# PCB1.net
KiCad netlist of a schematic drawn in EAGLE
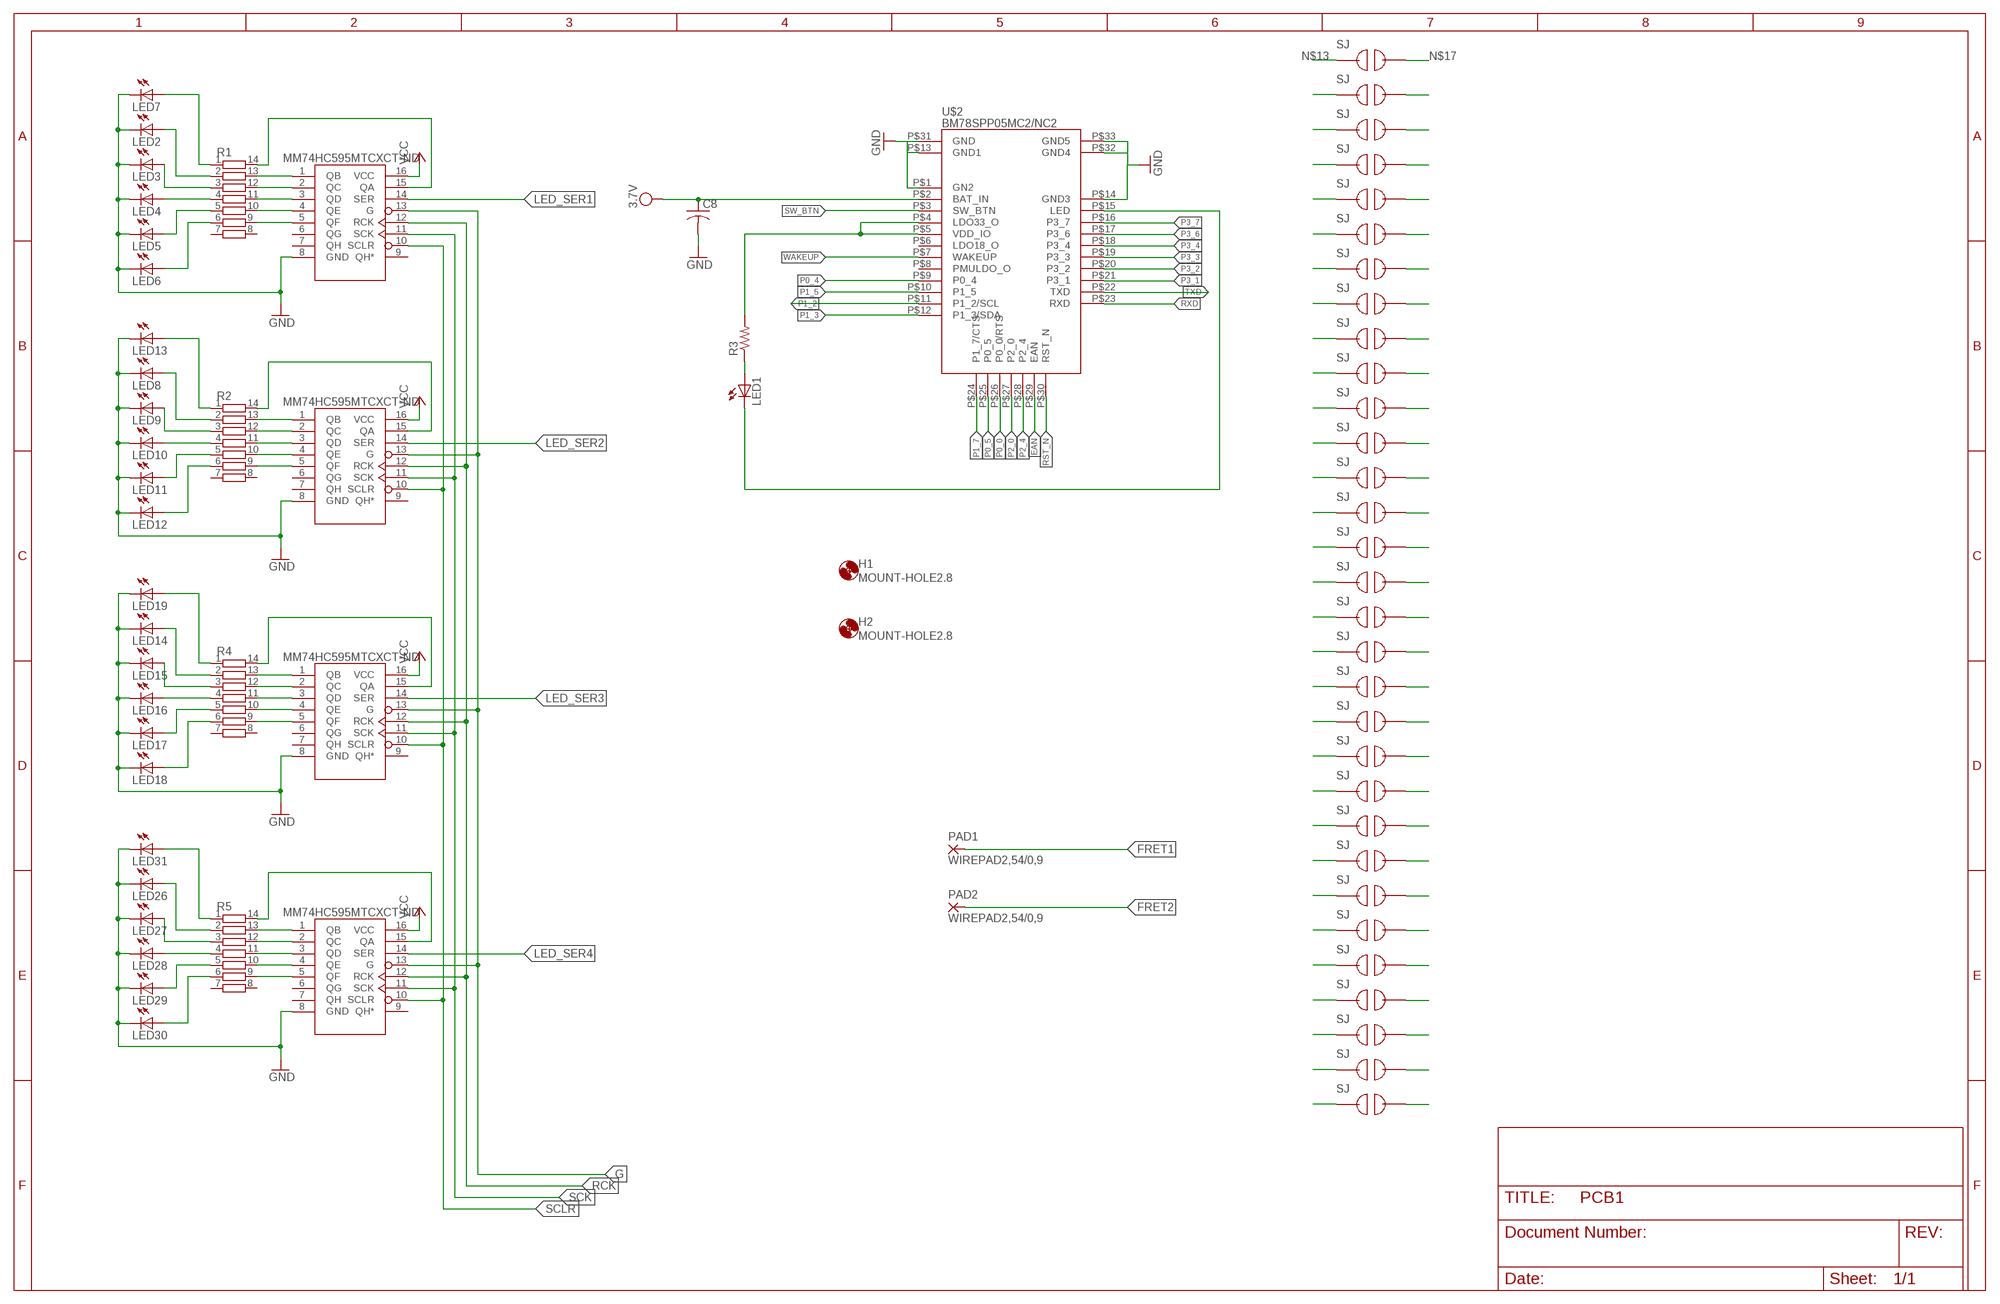
[diagram p0: schematic, sheet 1]

(export (version "E")
  (design (tool "Eeschema 10.0.6"))
  (components
    (comp (ref "C8")
      (value "C-USC0805")
      (footprint "eagle-import:C0805")
      (libsource (lib "eagle-import") (part "C-USC0805"))
    )
    (comp (ref "H1")
      (value "MOUNT-HOLE2.8")
      (footprint "eagle-import:2,8")
      (libsource (lib "eagle-import") (part "MOUNT-HOLE2.8"))
    )
    (comp (ref "H2")
      (value "MOUNT-HOLE2.8")
      (footprint "eagle-import:2,8")
      (libsource (lib "eagle-import") (part "MOUNT-HOLE2.8"))
    )
    (comp (ref "LED1")
      (value "LEDSMT1206")
      (footprint "eagle-import:1206")
      (libsource (lib "eagle-import") (part "LEDSMT1206"))
    )
    (comp (ref "LED2")
      (value "LEDSMT1206")
      (footprint "eagle-import:1206")
      (libsource (lib "eagle-import") (part "LEDSMT1206"))
    )
    (comp (ref "LED3")
      (value "LEDSMT1206")
      (footprint "eagle-import:1206")
      (libsource (lib "eagle-import") (part "LEDSMT1206"))
    )
    (comp (ref "LED4")
      (value "LEDSMT1206")
      (footprint "eagle-import:1206")
      (libsource (lib "eagle-import") (part "LEDSMT1206"))
    )
    (comp (ref "LED5")
      (value "LEDSMT1206")
      (footprint "eagle-import:1206")
      (libsource (lib "eagle-import") (part "LEDSMT1206"))
    )
    (comp (ref "LED6")
      (value "LEDSMT1206")
      (footprint "eagle-import:1206")
      (libsource (lib "eagle-import") (part "LEDSMT1206"))
    )
    (comp (ref "LED7")
      (value "LEDSMT1206")
      (footprint "eagle-import:1206")
      (libsource (lib "eagle-import") (part "LEDSMT1206"))
    )
    (comp (ref "LED8")
      (value "LEDSMT1206")
      (footprint "eagle-import:1206")
      (libsource (lib "eagle-import") (part "LEDSMT1206"))
    )
    (comp (ref "LED9")
      (value "LEDSMT1206")
      (footprint "eagle-import:1206")
      (libsource (lib "eagle-import") (part "LEDSMT1206"))
    )
    (comp (ref "LED10")
      (value "LEDSMT1206")
      (footprint "eagle-import:1206")
      (libsource (lib "eagle-import") (part "LEDSMT1206"))
    )
    (comp (ref "LED11")
      (value "LEDSMT1206")
      (footprint "eagle-import:1206")
      (libsource (lib "eagle-import") (part "LEDSMT1206"))
    )
    (comp (ref "LED12")
      (value "LEDSMT1206")
      (footprint "eagle-import:1206")
      (libsource (lib "eagle-import") (part "LEDSMT1206"))
    )
    (comp (ref "LED13")
      (value "LEDSMT1206")
      (footprint "eagle-import:1206")
      (libsource (lib "eagle-import") (part "LEDSMT1206"))
    )
    (comp (ref "LED14")
      (value "LEDSMT1206")
      (footprint "eagle-import:1206")
      (libsource (lib "eagle-import") (part "LEDSMT1206"))
    )
    (comp (ref "LED15")
      (value "LEDSMT1206")
      (footprint "eagle-import:1206")
      (libsource (lib "eagle-import") (part "LEDSMT1206"))
    )
    (comp (ref "LED16")
      (value "LEDSMT1206")
      (footprint "eagle-import:1206")
      (libsource (lib "eagle-import") (part "LEDSMT1206"))
    )
    (comp (ref "LED17")
      (value "LEDSMT1206")
      (footprint "eagle-import:1206")
      (libsource (lib "eagle-import") (part "LEDSMT1206"))
    )
    (comp (ref "LED18")
      (value "LEDSMT1206")
      (footprint "eagle-import:1206")
      (libsource (lib "eagle-import") (part "LEDSMT1206"))
    )
    (comp (ref "LED19")
      (value "LEDSMT1206")
      (footprint "eagle-import:1206")
      (libsource (lib "eagle-import") (part "LEDSMT1206"))
    )
    (comp (ref "LED26")
      (value "LEDSMT1206")
      (footprint "eagle-import:1206")
      (libsource (lib "eagle-import") (part "LEDSMT1206"))
    )
    (comp (ref "LED27")
      (value "LEDSMT1206")
      (footprint "eagle-import:1206")
      (libsource (lib "eagle-import") (part "LEDSMT1206"))
    )
    (comp (ref "LED28")
      (value "LEDSMT1206")
      (footprint "eagle-import:1206")
      (libsource (lib "eagle-import") (part "LEDSMT1206"))
    )
    (comp (ref "LED29")
      (value "LEDSMT1206")
      (footprint "eagle-import:1206")
      (libsource (lib "eagle-import") (part "LEDSMT1206"))
    )
    (comp (ref "LED30")
      (value "LEDSMT1206")
      (footprint "eagle-import:1206")
      (libsource (lib "eagle-import") (part "LEDSMT1206"))
    )
    (comp (ref "LED31")
      (value "LEDSMT1206")
      (footprint "eagle-import:1206")
      (libsource (lib "eagle-import") (part "LEDSMT1206"))
    )
    (comp (ref "PAD1")
      (value "WIREPAD2,54/0,9")
      (footprint "eagle-import:2,54_0,9")
      (libsource (lib "eagle-import") (part "WIREPAD2,54/0,9"))
    )
    (comp (ref "PAD2")
      (value "WIREPAD2,54/0,9")
      (footprint "eagle-import:2,54_0,9")
      (libsource (lib "eagle-import") (part "WIREPAD2,54/0,9"))
    )
    (comp (ref "R1")
      (value "4814P-T01")
      (footprint "eagle-import:4814P")
      (fields (field (name "MF") "BOURNS, INC.") (field (name "MPN") "4814P-T01-104LF"))
      (libsource (lib "eagle-import") (part "4814P-T01"))
    )
    (comp (ref "R2")
      (value "4814P-T01")
      (footprint "eagle-import:4814P")
      (fields (field (name "MF") "BOURNS, INC.") (field (name "MPN") "4814P-T01-104LF"))
      (libsource (lib "eagle-import") (part "4814P-T01"))
    )
    (comp (ref "R3")
      (value "R-US_M0805")
      (footprint "eagle-import:M0805")
      (libsource (lib "eagle-import") (part "R-US_M0805"))
    )
    (comp (ref "R4")
      (value "4814P-T01")
      (footprint "eagle-import:4814P")
      (fields (field (name "MF") "BOURNS, INC.") (field (name "MPN") "4814P-T01-104LF"))
      (libsource (lib "eagle-import") (part "4814P-T01"))
    )
    (comp (ref "R5")
      (value "4814P-T01")
      (footprint "eagle-import:4814P")
      (fields (field (name "MF") "BOURNS, INC.") (field (name "MPN") "4814P-T01-104LF"))
      (libsource (lib "eagle-import") (part "4814P-T01"))
    )
    (comp (ref "U$1")
      (value "MM74HC595TSSOP-LD16")
      (footprint "eagle-import:MM74HC595MTCXCT-ND")
      (libsource (lib "eagle-import") (part "MM74HC595TSSOP-LD16"))
    )
    (comp (ref "U$2")
      (value "BM78SPP05MC2/NC2")
      (footprint "eagle-import:BM78SPP05MC2_NC2")
      (libsource (lib "eagle-import") (part "BM78SPP05MC2/NC2"))
    )
    (comp (ref "U$3")
      (value "MM74HC595TSSOP-LD16")
      (footprint "eagle-import:MM74HC595MTCXCT-ND")
      (libsource (lib "eagle-import") (part "MM74HC595TSSOP-LD16"))
    )
    (comp (ref "U$4")
      (value "MM74HC595TSSOP-LD16")
      (footprint "eagle-import:MM74HC595MTCXCT-ND")
      (libsource (lib "eagle-import") (part "MM74HC595TSSOP-LD16"))
    )
    (comp (ref "U$5")
      (value "MM74HC595TSSOP-LD16")
      (footprint "eagle-import:MM74HC595MTCXCT-ND")
      (libsource (lib "eagle-import") (part "MM74HC595TSSOP-LD16"))
    )
    (comp (ref "U$6")
      (value "JUMPER")
      (footprint "eagle-import:JUMPER")
      (libsource (lib "eagle-import") (part "JUMPER"))
    )
    (comp (ref "U$7")
      (value "JUMPER")
      (footprint "eagle-import:JUMPER")
      (libsource (lib "eagle-import") (part "JUMPER"))
    )
    (comp (ref "U$8")
      (value "JUMPER")
      (footprint "eagle-import:JUMPER")
      (libsource (lib "eagle-import") (part "JUMPER"))
    )
    (comp (ref "U$9")
      (value "JUMPER")
      (footprint "eagle-import:JUMPER")
      (libsource (lib "eagle-import") (part "JUMPER"))
    )
    (comp (ref "U$10")
      (value "JUMPER")
      (footprint "eagle-import:JUMPER")
      (libsource (lib "eagle-import") (part "JUMPER"))
    )
    (comp (ref "U$11")
      (value "JUMPER")
      (footprint "eagle-import:JUMPER")
      (libsource (lib "eagle-import") (part "JUMPER"))
    )
    (comp (ref "U$12")
      (value "JUMPER")
      (footprint "eagle-import:JUMPER")
      (libsource (lib "eagle-import") (part "JUMPER"))
    )
    (comp (ref "U$13")
      (value "JUMPER")
      (footprint "eagle-import:JUMPER")
      (libsource (lib "eagle-import") (part "JUMPER"))
    )
    (comp (ref "U$14")
      (value "JUMPER")
      (footprint "eagle-import:JUMPER")
      (libsource (lib "eagle-import") (part "JUMPER"))
    )
    (comp (ref "U$15")
      (value "JUMPER")
      (footprint "eagle-import:JUMPER")
      (libsource (lib "eagle-import") (part "JUMPER"))
    )
    (comp (ref "U$16")
      (value "JUMPER")
      (footprint "eagle-import:JUMPER")
      (libsource (lib "eagle-import") (part "JUMPER"))
    )
    (comp (ref "U$17")
      (value "JUMPER")
      (footprint "eagle-import:JUMPER")
      (libsource (lib "eagle-import") (part "JUMPER"))
    )
    (comp (ref "U$18")
      (value "JUMPER")
      (footprint "eagle-import:JUMPER")
      (libsource (lib "eagle-import") (part "JUMPER"))
    )
    (comp (ref "U$19")
      (value "JUMPER")
      (footprint "eagle-import:JUMPER")
      (libsource (lib "eagle-import") (part "JUMPER"))
    )
    (comp (ref "U$20")
      (value "JUMPER")
      (footprint "eagle-import:JUMPER")
      (libsource (lib "eagle-import") (part "JUMPER"))
    )
    (comp (ref "U$21")
      (value "JUMPER")
      (footprint "eagle-import:JUMPER")
      (libsource (lib "eagle-import") (part "JUMPER"))
    )
    (comp (ref "U$22")
      (value "JUMPER")
      (footprint "eagle-import:JUMPER")
      (libsource (lib "eagle-import") (part "JUMPER"))
    )
    (comp (ref "U$23")
      (value "JUMPER")
      (footprint "eagle-import:JUMPER")
      (libsource (lib "eagle-import") (part "JUMPER"))
    )
    (comp (ref "U$24")
      (value "JUMPER")
      (footprint "eagle-import:JUMPER")
      (libsource (lib "eagle-import") (part "JUMPER"))
    )
    (comp (ref "U$25")
      (value "JUMPER")
      (footprint "eagle-import:JUMPER")
      (libsource (lib "eagle-import") (part "JUMPER"))
    )
    (comp (ref "U$26")
      (value "JUMPER")
      (footprint "eagle-import:JUMPER")
      (libsource (lib "eagle-import") (part "JUMPER"))
    )
    (comp (ref "U$27")
      (value "JUMPER")
      (footprint "eagle-import:JUMPER")
      (libsource (lib "eagle-import") (part "JUMPER"))
    )
    (comp (ref "U$28")
      (value "JUMPER")
      (footprint "eagle-import:JUMPER")
      (libsource (lib "eagle-import") (part "JUMPER"))
    )
    (comp (ref "U$29")
      (value "JUMPER")
      (footprint "eagle-import:JUMPER")
      (libsource (lib "eagle-import") (part "JUMPER"))
    )
    (comp (ref "U$30")
      (value "JUMPER")
      (footprint "eagle-import:JUMPER")
      (libsource (lib "eagle-import") (part "JUMPER"))
    )
    (comp (ref "U$31")
      (value "JUMPER")
      (footprint "eagle-import:JUMPER")
      (libsource (lib "eagle-import") (part "JUMPER"))
    )
    (comp (ref "U$32")
      (value "JUMPER")
      (footprint "eagle-import:JUMPER")
      (libsource (lib "eagle-import") (part "JUMPER"))
    )
    (comp (ref "U$33")
      (value "JUMPER")
      (footprint "eagle-import:JUMPER")
      (libsource (lib "eagle-import") (part "JUMPER"))
    )
    (comp (ref "U$34")
      (value "JUMPER")
      (footprint "eagle-import:JUMPER")
      (libsource (lib "eagle-import") (part "JUMPER"))
    )
    (comp (ref "U$35")
      (value "JUMPER")
      (footprint "eagle-import:JUMPER")
      (libsource (lib "eagle-import") (part "JUMPER"))
    )
    (comp (ref "U$36")
      (value "JUMPER")
      (footprint "eagle-import:JUMPER")
      (libsource (lib "eagle-import") (part "JUMPER"))
    )
  )
  (nets
    (net (code "1") (name "/N$13") (class "Default")
      (node (ref "U$35") (pin "P$1") (pinfunction "P$1_P$1") (pintype "bidirectional"))
    )
    (net (code "2") (name "/N$17") (class "Default")
      (node (ref "U$35") (pin "P$2") (pinfunction "P$2_P$2") (pintype "bidirectional"))
    )
    (net (code "3") (name "3.7V") (class "Default")
      (node (ref "C8") (pin "1") (pinfunction "1_1") (pintype "passive"))
      (node (ref "U$2") (pin "P$2") (pinfunction "BAT_IN_P$2") (pintype "bidirectional"))
    )
    (net (code "4") (name "EAN") (class "Default")
      (node (ref "U$2") (pin "P$29") (pinfunction "EAN_P$29") (pintype "bidirectional"))
    )
    (net (code "5") (name "FRET1") (class "Default")
      (node (ref "PAD1") (pin "1") (pinfunction "P_1") (pintype "passive"))
    )
    (net (code "6") (name "FRET2") (class "Default")
      (node (ref "PAD2") (pin "1") (pinfunction "P_1") (pintype "passive"))
    )
    (net (code "7") (name "G") (class "Default")
      (node (ref "U$1") (pin "13") (pinfunction "G_13") (pintype "bidirectional"))
      (node (ref "U$3") (pin "13") (pinfunction "G_13") (pintype "bidirectional"))
      (node (ref "U$4") (pin "13") (pinfunction "G_13") (pintype "bidirectional"))
      (node (ref "U$5") (pin "13") (pinfunction "G_13") (pintype "bidirectional"))
    )
    (net (code "8") (name "GND") (class "Default")
      (node (ref "C8") (pin "2") (pinfunction "2_2") (pintype "passive"))
      (node (ref "LED10") (pin "C") (pinfunction "C_C") (pintype "passive"))
      (node (ref "LED11") (pin "C") (pinfunction "C_C") (pintype "passive"))
      (node (ref "LED12") (pin "C") (pinfunction "C_C") (pintype "passive"))
      (node (ref "LED13") (pin "C") (pinfunction "C_C") (pintype "passive"))
      (node (ref "LED14") (pin "C") (pinfunction "C_C") (pintype "passive"))
      (node (ref "LED15") (pin "C") (pinfunction "C_C") (pintype "passive"))
      (node (ref "LED16") (pin "C") (pinfunction "C_C") (pintype "passive"))
      (node (ref "LED17") (pin "C") (pinfunction "C_C") (pintype "passive"))
      (node (ref "LED18") (pin "C") (pinfunction "C_C") (pintype "passive"))
      (node (ref "LED19") (pin "C") (pinfunction "C_C") (pintype "passive"))
      (node (ref "LED2") (pin "C") (pinfunction "C_C") (pintype "passive"))
      (node (ref "LED26") (pin "C") (pinfunction "C_C") (pintype "passive"))
      (node (ref "LED27") (pin "C") (pinfunction "C_C") (pintype "passive"))
      (node (ref "LED28") (pin "C") (pinfunction "C_C") (pintype "passive"))
      (node (ref "LED29") (pin "C") (pinfunction "C_C") (pintype "passive"))
      (node (ref "LED3") (pin "C") (pinfunction "C_C") (pintype "passive"))
      (node (ref "LED30") (pin "C") (pinfunction "C_C") (pintype "passive"))
      (node (ref "LED31") (pin "C") (pinfunction "C_C") (pintype "passive"))
      (node (ref "LED4") (pin "C") (pinfunction "C_C") (pintype "passive"))
      (node (ref "LED5") (pin "C") (pinfunction "C_C") (pintype "passive"))
      (node (ref "LED6") (pin "C") (pinfunction "C_C") (pintype "passive"))
      (node (ref "LED7") (pin "C") (pinfunction "C_C") (pintype "passive"))
      (node (ref "LED8") (pin "C") (pinfunction "C_C") (pintype "passive"))
      (node (ref "LED9") (pin "C") (pinfunction "C_C") (pintype "passive"))
      (node (ref "U$1") (pin "8") (pinfunction "GND_8") (pintype "bidirectional"))
      (node (ref "U$2") (pin "P$1") (pinfunction "GN2_P$1") (pintype "bidirectional"))
      (node (ref "U$2") (pin "P$13") (pinfunction "GND1_P$13") (pintype "bidirectional"))
      (node (ref "U$2") (pin "P$14") (pinfunction "GND3_P$14") (pintype "bidirectional"))
      (node (ref "U$2") (pin "P$31") (pinfunction "GND_P$31") (pintype "bidirectional"))
      (node (ref "U$2") (pin "P$32") (pinfunction "GND4_P$32") (pintype "bidirectional"))
      (node (ref "U$2") (pin "P$33") (pinfunction "GND5_P$33") (pintype "bidirectional"))
      (node (ref "U$3") (pin "8") (pinfunction "GND_8") (pintype "bidirectional"))
      (node (ref "U$4") (pin "8") (pinfunction "GND_8") (pintype "bidirectional"))
      (node (ref "U$5") (pin "8") (pinfunction "GND_8") (pintype "bidirectional"))
    )
    (net (code "9") (name "LED_SER1") (class "Default")
      (node (ref "U$4") (pin "14") (pinfunction "SER_14") (pintype "bidirectional"))
    )
    (net (code "10") (name "LED_SER2") (class "Default")
      (node (ref "U$1") (pin "14") (pinfunction "SER_14") (pintype "bidirectional"))
    )
    (net (code "11") (name "LED_SER3") (class "Default")
      (node (ref "U$3") (pin "14") (pinfunction "SER_14") (pintype "bidirectional"))
    )
    (net (code "12") (name "LED_SER4") (class "Default")
      (node (ref "U$5") (pin "14") (pinfunction "SER_14") (pintype "bidirectional"))
    )
    (net (code "13") (name "Net-(LED1-PadA)") (class "Default")
      (node (ref "LED1") (pin "A") (pinfunction "A_A") (pintype "passive"))
      (node (ref "R3") (pin "1") (pinfunction "1_1") (pintype "passive"))
    )
    (net (code "14") (name "Net-(LED2-PadA)") (class "Default")
      (node (ref "LED2") (pin "A") (pinfunction "A_A") (pintype "passive"))
      (node (ref "R1") (pin "2") (pinfunction "2_2") (pintype "passive"))
    )
    (net (code "15") (name "Net-(LED3-PadA)") (class "Default")
      (node (ref "LED3") (pin "A") (pinfunction "A_A") (pintype "passive"))
      (node (ref "R1") (pin "3") (pinfunction "3_3") (pintype "passive"))
    )
    (net (code "16") (name "Net-(LED4-PadA)") (class "Default")
      (node (ref "LED4") (pin "A") (pinfunction "A_A") (pintype "passive"))
      (node (ref "R1") (pin "4") (pinfunction "4_4") (pintype "passive"))
    )
    (net (code "17") (name "Net-(LED5-PadA)") (class "Default")
      (node (ref "LED5") (pin "A") (pinfunction "A_A") (pintype "passive"))
      (node (ref "R1") (pin "5") (pinfunction "5_5") (pintype "passive"))
    )
    (net (code "18") (name "Net-(LED6-PadA)") (class "Default")
      (node (ref "LED6") (pin "A") (pinfunction "A_A") (pintype "passive"))
      (node (ref "R1") (pin "6") (pinfunction "6_6") (pintype "passive"))
    )
    (net (code "19") (name "Net-(LED7-PadA)") (class "Default")
      (node (ref "LED7") (pin "A") (pinfunction "A_A") (pintype "passive"))
      (node (ref "R1") (pin "1") (pinfunction "1_1") (pintype "passive"))
    )
    (net (code "20") (name "Net-(LED8-PadA)") (class "Default")
      (node (ref "LED8") (pin "A") (pinfunction "A_A") (pintype "passive"))
      (node (ref "R2") (pin "2") (pinfunction "2_2") (pintype "passive"))
    )
    (net (code "21") (name "Net-(LED9-PadA)") (class "Default")
      (node (ref "LED9") (pin "A") (pinfunction "A_A") (pintype "passive"))
      (node (ref "R2") (pin "3") (pinfunction "3_3") (pintype "passive"))
    )
    (net (code "22") (name "Net-(LED10-PadA)") (class "Default")
      (node (ref "LED10") (pin "A") (pinfunction "A_A") (pintype "passive"))
      (node (ref "R2") (pin "4") (pinfunction "4_4") (pintype "passive"))
    )
    (net (code "23") (name "Net-(LED11-PadA)") (class "Default")
      (node (ref "LED11") (pin "A") (pinfunction "A_A") (pintype "passive"))
      (node (ref "R2") (pin "5") (pinfunction "5_5") (pintype "passive"))
    )
    (net (code "24") (name "Net-(LED12-PadA)") (class "Default")
      (node (ref "LED12") (pin "A") (pinfunction "A_A") (pintype "passive"))
      (node (ref "R2") (pin "6") (pinfunction "6_6") (pintype "passive"))
    )
    (net (code "25") (name "Net-(LED13-PadA)") (class "Default")
      (node (ref "LED13") (pin "A") (pinfunction "A_A") (pintype "passive"))
      (node (ref "R2") (pin "1") (pinfunction "1_1") (pintype "passive"))
    )
    (net (code "26") (name "Net-(LED14-PadA)") (class "Default")
      (node (ref "LED14") (pin "A") (pinfunction "A_A") (pintype "passive"))
      (node (ref "R4") (pin "2") (pinfunction "2_2") (pintype "passive"))
    )
    (net (code "27") (name "Net-(LED15-PadA)") (class "Default")
      (node (ref "LED15") (pin "A") (pinfunction "A_A") (pintype "passive"))
      (node (ref "R4") (pin "3") (pinfunction "3_3") (pintype "passive"))
    )
    (net (code "28") (name "Net-(LED16-PadA)") (class "Default")
      (node (ref "LED16") (pin "A") (pinfunction "A_A") (pintype "passive"))
      (node (ref "R4") (pin "4") (pinfunction "4_4") (pintype "passive"))
    )
    (net (code "29") (name "Net-(LED17-PadA)") (class "Default")
      (node (ref "LED17") (pin "A") (pinfunction "A_A") (pintype "passive"))
      (node (ref "R4") (pin "5") (pinfunction "5_5") (pintype "passive"))
    )
    (net (code "30") (name "Net-(LED18-PadA)") (class "Default")
      (node (ref "LED18") (pin "A") (pinfunction "A_A") (pintype "passive"))
      (node (ref "R4") (pin "6") (pinfunction "6_6") (pintype "passive"))
    )
    (net (code "31") (name "Net-(LED19-PadA)") (class "Default")
      (node (ref "LED19") (pin "A") (pinfunction "A_A") (pintype "passive"))
      (node (ref "R4") (pin "1") (pinfunction "1_1") (pintype "passive"))
    )
    (net (code "32") (name "Net-(LED26-PadA)") (class "Default")
      (node (ref "LED26") (pin "A") (pinfunction "A_A") (pintype "passive"))
      (node (ref "R5") (pin "2") (pinfunction "2_2") (pintype "passive"))
    )
    (net (code "33") (name "Net-(LED27-PadA)") (class "Default")
      (node (ref "LED27") (pin "A") (pinfunction "A_A") (pintype "passive"))
      (node (ref "R5") (pin "3") (pinfunction "3_3") (pintype "passive"))
    )
    (net (code "34") (name "Net-(LED28-PadA)") (class "Default")
      (node (ref "LED28") (pin "A") (pinfunction "A_A") (pintype "passive"))
      (node (ref "R5") (pin "4") (pinfunction "4_4") (pintype "passive"))
    )
    (net (code "35") (name "Net-(LED29-PadA)") (class "Default")
      (node (ref "LED29") (pin "A") (pinfunction "A_A") (pintype "passive"))
      (node (ref "R5") (pin "5") (pinfunction "5_5") (pintype "passive"))
    )
    (net (code "36") (name "Net-(LED30-PadA)") (class "Default")
      (node (ref "LED30") (pin "A") (pinfunction "A_A") (pintype "passive"))
      (node (ref "R5") (pin "6") (pinfunction "6_6") (pintype "passive"))
    )
    (net (code "37") (name "Net-(LED31-PadA)") (class "Default")
      (node (ref "LED31") (pin "A") (pinfunction "A_A") (pintype "passive"))
      (node (ref "R5") (pin "1") (pinfunction "1_1") (pintype "passive"))
    )
    (net (code "38") (name "Net-(U$1-QA)") (class "Default")
      (node (ref "R2") (pin "14") (pinfunction "14_14") (pintype "passive"))
      (node (ref "U$1") (pin "15") (pinfunction "QA_15") (pintype "bidirectional"))
    )
    (net (code "39") (name "Net-(U$1-QB)") (class "Default")
      (node (ref "R2") (pin "13") (pinfunction "13_13") (pintype "passive"))
      (node (ref "U$1") (pin "1") (pinfunction "QB_1") (pintype "bidirectional"))
    )
    (net (code "40") (name "Net-(U$1-QC)") (class "Default")
      (node (ref "R2") (pin "12") (pinfunction "12_12") (pintype "passive"))
      (node (ref "U$1") (pin "2") (pinfunction "QC_2") (pintype "bidirectional"))
    )
    (net (code "41") (name "Net-(U$1-QD)") (class "Default")
      (node (ref "R2") (pin "11") (pinfunction "11_11") (pintype "passive"))
      (node (ref "U$1") (pin "3") (pinfunction "QD_3") (pintype "bidirectional"))
    )
    (net (code "42") (name "Net-(U$1-QE)") (class "Default")
      (node (ref "R2") (pin "10") (pinfunction "10_10") (pintype "passive"))
      (node (ref "U$1") (pin "4") (pinfunction "QE_4") (pintype "bidirectional"))
    )
    (net (code "43") (name "Net-(U$1-QF)") (class "Default")
      (node (ref "R2") (pin "9") (pinfunction "9_9") (pintype "passive"))
      (node (ref "U$1") (pin "5") (pinfunction "QF_5") (pintype "bidirectional"))
    )
    (net (code "44") (name "Net-(U$2-LDO33_O)") (class "Default")
      (node (ref "R3") (pin "2") (pinfunction "2_2") (pintype "passive"))
      (node (ref "U$2") (pin "P$4") (pinfunction "LDO33_O_P$4") (pintype "bidirectional"))
      (node (ref "U$2") (pin "P$5") (pinfunction "VDD_IO_P$5") (pintype "bidirectional"))
    )
    (net (code "45") (name "Net-(U$2-LED)") (class "Default")
      (node (ref "LED1") (pin "C") (pinfunction "C_C") (pintype "passive"))
      (node (ref "U$2") (pin "P$15") (pinfunction "LED_P$15") (pintype "bidirectional"))
    )
    (net (code "46") (name "Net-(U$3-QA)") (class "Default")
      (node (ref "R4") (pin "14") (pinfunction "14_14") (pintype "passive"))
      (node (ref "U$3") (pin "15") (pinfunction "QA_15") (pintype "bidirectional"))
    )
    (net (code "47") (name "Net-(U$3-QB)") (class "Default")
      (node (ref "R4") (pin "13") (pinfunction "13_13") (pintype "passive"))
      (node (ref "U$3") (pin "1") (pinfunction "QB_1") (pintype "bidirectional"))
    )
    (net (code "48") (name "Net-(U$3-QC)") (class "Default")
      (node (ref "R4") (pin "12") (pinfunction "12_12") (pintype "passive"))
      (node (ref "U$3") (pin "2") (pinfunction "QC_2") (pintype "bidirectional"))
    )
    (net (code "49") (name "Net-(U$3-QD)") (class "Default")
      (node (ref "R4") (pin "11") (pinfunction "11_11") (pintype "passive"))
      (node (ref "U$3") (pin "3") (pinfunction "QD_3") (pintype "bidirectional"))
    )
    (net (code "50") (name "Net-(U$3-QE)") (class "Default")
      (node (ref "R4") (pin "10") (pinfunction "10_10") (pintype "passive"))
      (node (ref "U$3") (pin "4") (pinfunction "QE_4") (pintype "bidirectional"))
    )
    (net (code "51") (name "Net-(U$3-QF)") (class "Default")
      (node (ref "R4") (pin "9") (pinfunction "9_9") (pintype "passive"))
      (node (ref "U$3") (pin "5") (pinfunction "QF_5") (pintype "bidirectional"))
    )
    (net (code "52") (name "Net-(U$4-QA)") (class "Default")
      (node (ref "R1") (pin "14") (pinfunction "14_14") (pintype "passive"))
      (node (ref "U$4") (pin "15") (pinfunction "QA_15") (pintype "bidirectional"))
    )
    (net (code "53") (name "Net-(U$4-QB)") (class "Default")
      (node (ref "R1") (pin "13") (pinfunction "13_13") (pintype "passive"))
      (node (ref "U$4") (pin "1") (pinfunction "QB_1") (pintype "bidirectional"))
    )
    (net (code "54") (name "Net-(U$4-QC)") (class "Default")
      (node (ref "R1") (pin "12") (pinfunction "12_12") (pintype "passive"))
      (node (ref "U$4") (pin "2") (pinfunction "QC_2") (pintype "bidirectional"))
    )
    (net (code "55") (name "Net-(U$4-QD)") (class "Default")
      (node (ref "R1") (pin "11") (pinfunction "11_11") (pintype "passive"))
      (node (ref "U$4") (pin "3") (pinfunction "QD_3") (pintype "bidirectional"))
    )
    (net (code "56") (name "Net-(U$4-QE)") (class "Default")
      (node (ref "R1") (pin "10") (pinfunction "10_10") (pintype "passive"))
      (node (ref "U$4") (pin "4") (pinfunction "QE_4") (pintype "bidirectional"))
    )
    (net (code "57") (name "Net-(U$4-QF)") (class "Default")
      (node (ref "R1") (pin "9") (pinfunction "9_9") (pintype "passive"))
      (node (ref "U$4") (pin "5") (pinfunction "QF_5") (pintype "bidirectional"))
    )
    (net (code "58") (name "Net-(U$5-QA)") (class "Default")
      (node (ref "R5") (pin "14") (pinfunction "14_14") (pintype "passive"))
      (node (ref "U$5") (pin "15") (pinfunction "QA_15") (pintype "bidirectional"))
    )
    (net (code "59") (name "Net-(U$5-QB)") (class "Default")
      (node (ref "R5") (pin "13") (pinfunction "13_13") (pintype "passive"))
      (node (ref "U$5") (pin "1") (pinfunction "QB_1") (pintype "bidirectional"))
    )
    (net (code "60") (name "Net-(U$5-QC)") (class "Default")
      (node (ref "R5") (pin "12") (pinfunction "12_12") (pintype "passive"))
      (node (ref "U$5") (pin "2") (pinfunction "QC_2") (pintype "bidirectional"))
    )
    (net (code "61") (name "Net-(U$5-QD)") (class "Default")
      (node (ref "R5") (pin "11") (pinfunction "11_11") (pintype "passive"))
      (node (ref "U$5") (pin "3") (pinfunction "QD_3") (pintype "bidirectional"))
    )
    (net (code "62") (name "Net-(U$5-QE)") (class "Default")
      (node (ref "R5") (pin "10") (pinfunction "10_10") (pintype "passive"))
      (node (ref "U$5") (pin "4") (pinfunction "QE_4") (pintype "bidirectional"))
    )
    (net (code "63") (name "Net-(U$5-QF)") (class "Default")
      (node (ref "R5") (pin "9") (pinfunction "9_9") (pintype "passive"))
      (node (ref "U$5") (pin "5") (pinfunction "QF_5") (pintype "bidirectional"))
    )
    (net (code "64") (name "P0_0") (class "Default")
      (node (ref "U$2") (pin "P$26") (pinfunction "P0_0/RTS_P$26") (pintype "bidirectional"))
    )
    (net (code "65") (name "P0_4") (class "Default")
      (node (ref "U$2") (pin "P$9") (pinfunction "P0_4_P$9") (pintype "bidirectional"))
    )
    (net (code "66") (name "P0_5") (class "Default")
      (node (ref "U$2") (pin "P$25") (pinfunction "P0_5_P$25") (pintype "bidirectional"))
    )
    (net (code "67") (name "P1_2") (class "Default")
      (node (ref "U$2") (pin "P$11") (pinfunction "P1_2/SCL_P$11") (pintype "bidirectional"))
    )
    (net (code "68") (name "P1_3") (class "Default")
      (node (ref "U$2") (pin "P$12") (pinfunction "P1_3/SDA_P$12") (pintype "bidirectional"))
    )
    (net (code "69") (name "P1_5") (class "Default")
      (node (ref "U$2") (pin "P$10") (pinfunction "P1_5_P$10") (pintype "bidirectional"))
    )
    (net (code "70") (name "P1_7") (class "Default")
      (node (ref "U$2") (pin "P$24") (pinfunction "P1_7/CTS_P$24") (pintype "bidirectional"))
    )
    (net (code "71") (name "P2_0") (class "Default")
      (node (ref "U$2") (pin "P$27") (pinfunction "P2_0_P$27") (pintype "bidirectional"))
    )
    (net (code "72") (name "P2_4") (class "Default")
      (node (ref "U$2") (pin "P$28") (pinfunction "P2_4_P$28") (pintype "bidirectional"))
    )
    (net (code "73") (name "P3_1") (class "Default")
      (node (ref "U$2") (pin "P$21") (pinfunction "P3_1_P$21") (pintype "bidirectional"))
    )
    (net (code "74") (name "P3_2") (class "Default")
      (node (ref "U$2") (pin "P$20") (pinfunction "P3_2_P$20") (pintype "bidirectional"))
    )
    (net (code "75") (name "P3_3") (class "Default")
      (node (ref "U$2") (pin "P$19") (pinfunction "P3_3_P$19") (pintype "bidirectional"))
    )
    (net (code "76") (name "P3_4") (class "Default")
      (node (ref "U$2") (pin "P$18") (pinfunction "P3_4_P$18") (pintype "bidirectional"))
    )
    (net (code "77") (name "P3_6") (class "Default")
      (node (ref "U$2") (pin "P$17") (pinfunction "P3_6_P$17") (pintype "bidirectional"))
    )
    (net (code "78") (name "P3_7") (class "Default")
      (node (ref "U$2") (pin "P$16") (pinfunction "P3_7_P$16") (pintype "bidirectional"))
    )
    (net (code "79") (name "RCK") (class "Default")
      (node (ref "U$1") (pin "12") (pinfunction "RCK_12") (pintype "bidirectional"))
      (node (ref "U$3") (pin "12") (pinfunction "RCK_12") (pintype "bidirectional"))
      (node (ref "U$4") (pin "12") (pinfunction "RCK_12") (pintype "bidirectional"))
      (node (ref "U$5") (pin "12") (pinfunction "RCK_12") (pintype "bidirectional"))
    )
    (net (code "80") (name "RST_N") (class "Default")
      (node (ref "U$2") (pin "P$30") (pinfunction "RST_N_P$30") (pintype "bidirectional"))
    )
    (net (code "81") (name "RXD") (class "Default")
      (node (ref "U$2") (pin "P$23") (pinfunction "RXD_P$23") (pintype "bidirectional"))
    )
    (net (code "82") (name "SCK") (class "Default")
      (node (ref "U$1") (pin "11") (pinfunction "SCK_11") (pintype "bidirectional"))
      (node (ref "U$3") (pin "11") (pinfunction "SCK_11") (pintype "bidirectional"))
      (node (ref "U$4") (pin "11") (pinfunction "SCK_11") (pintype "bidirectional"))
      (node (ref "U$5") (pin "11") (pinfunction "SCK_11") (pintype "bidirectional"))
    )
    (net (code "83") (name "SCLR") (class "Default")
      (node (ref "U$1") (pin "10") (pinfunction "SCLR_10") (pintype "bidirectional"))
      (node (ref "U$3") (pin "10") (pinfunction "SCLR_10") (pintype "bidirectional"))
      (node (ref "U$4") (pin "10") (pinfunction "SCLR_10") (pintype "bidirectional"))
      (node (ref "U$5") (pin "10") (pinfunction "SCLR_10") (pintype "bidirectional"))
    )
    (net (code "84") (name "SW_BTN") (class "Default")
      (node (ref "U$2") (pin "P$3") (pinfunction "SW_BTN_P$3") (pintype "bidirectional"))
    )
    (net (code "85") (name "TXD") (class "Default")
      (node (ref "U$2") (pin "P$22") (pinfunction "TXD_P$22") (pintype "bidirectional"))
    )
    (net (code "86") (name "VCC") (class "Default")
      (node (ref "U$1") (pin "16") (pinfunction "VCC_16") (pintype "bidirectional"))
      (node (ref "U$3") (pin "16") (pinfunction "VCC_16") (pintype "bidirectional"))
      (node (ref "U$4") (pin "16") (pinfunction "VCC_16") (pintype "bidirectional"))
      (node (ref "U$5") (pin "16") (pinfunction "VCC_16") (pintype "bidirectional"))
    )
    (net (code "87") (name "WAKEUP") (class "Default")
      (node (ref "U$2") (pin "P$7") (pinfunction "WAKEUP_P$7") (pintype "bidirectional"))
    )
    (net (code "88") (name "unconnected-(R1-Pad7)") (class "Default")
      (node (ref "R1") (pin "7") (pinfunction "7_7") (pintype "passive"))
    )
    (net (code "89") (name "unconnected-(R1-Pad8)") (class "Default")
      (node (ref "R1") (pin "8") (pinfunction "8_8") (pintype "passive"))
    )
    (net (code "90") (name "unconnected-(R2-Pad7)") (class "Default")
      (node (ref "R2") (pin "7") (pinfunction "7_7") (pintype "passive"))
    )
    (net (code "91") (name "unconnected-(R2-Pad8)") (class "Default")
      (node (ref "R2") (pin "8") (pinfunction "8_8") (pintype "passive"))
    )
    (net (code "92") (name "unconnected-(R4-Pad7)") (class "Default")
      (node (ref "R4") (pin "7") (pinfunction "7_7") (pintype "passive"))
    )
    (net (code "93") (name "unconnected-(R4-Pad8)") (class "Default")
      (node (ref "R4") (pin "8") (pinfunction "8_8") (pintype "passive"))
    )
    (net (code "94") (name "unconnected-(R5-Pad7)") (class "Default")
      (node (ref "R5") (pin "7") (pinfunction "7_7") (pintype "passive"))
    )
    (net (code "95") (name "unconnected-(R5-Pad8)") (class "Default")
      (node (ref "R5") (pin "8") (pinfunction "8_8") (pintype "passive"))
    )
    (net (code "96") (name "unconnected-(U$1-QG-Pad6)") (class "Default")
      (node (ref "U$1") (pin "6") (pinfunction "QG_6") (pintype "bidirectional"))
    )
    (net (code "97") (name "unconnected-(U$1-QH*-Pad9)") (class "Default")
      (node (ref "U$1") (pin "9") (pinfunction "QH*_9") (pintype "bidirectional"))
    )
    (net (code "98") (name "unconnected-(U$1-QH-Pad7)") (class "Default")
      (node (ref "U$1") (pin "7") (pinfunction "QH_7") (pintype "bidirectional"))
    )
    (net (code "99") (name "unconnected-(U$2-LDO18_O-PadP$6)") (class "Default")
      (node (ref "U$2") (pin "P$6") (pinfunction "LDO18_O_P$6") (pintype "bidirectional"))
    )
    (net (code "100") (name "unconnected-(U$2-PMULDO_O-PadP$8)") (class "Default")
      (node (ref "U$2") (pin "P$8") (pinfunction "PMULDO_O_P$8") (pintype "bidirectional"))
    )
    (net (code "101") (name "unconnected-(U$3-QG-Pad6)") (class "Default")
      (node (ref "U$3") (pin "6") (pinfunction "QG_6") (pintype "bidirectional"))
    )
    (net (code "102") (name "unconnected-(U$3-QH*-Pad9)") (class "Default")
      (node (ref "U$3") (pin "9") (pinfunction "QH*_9") (pintype "bidirectional"))
    )
    (net (code "103") (name "unconnected-(U$3-QH-Pad7)") (class "Default")
      (node (ref "U$3") (pin "7") (pinfunction "QH_7") (pintype "bidirectional"))
    )
    (net (code "104") (name "unconnected-(U$4-QG-Pad6)") (class "Default")
      (node (ref "U$4") (pin "6") (pinfunction "QG_6") (pintype "bidirectional"))
    )
    (net (code "105") (name "unconnected-(U$4-QH*-Pad9)") (class "Default")
      (node (ref "U$4") (pin "9") (pinfunction "QH*_9") (pintype "bidirectional"))
    )
    (net (code "106") (name "unconnected-(U$4-QH-Pad7)") (class "Default")
      (node (ref "U$4") (pin "7") (pinfunction "QH_7") (pintype "bidirectional"))
    )
    (net (code "107") (name "unconnected-(U$5-QG-Pad6)") (class "Default")
      (node (ref "U$5") (pin "6") (pinfunction "QG_6") (pintype "bidirectional"))
    )
    (net (code "108") (name "unconnected-(U$5-QH*-Pad9)") (class "Default")
      (node (ref "U$5") (pin "9") (pinfunction "QH*_9") (pintype "bidirectional"))
    )
    (net (code "109") (name "unconnected-(U$5-QH-Pad7)") (class "Default")
      (node (ref "U$5") (pin "7") (pinfunction "QH_7") (pintype "bidirectional"))
    )
    (net (code "110") (name "unconnected-(U$6-PadP$1)") (class "Default")
      (node (ref "U$6") (pin "P$1") (pinfunction "P$1_P$1") (pintype "bidirectional"))
    )
    (net (code "111") (name "unconnected-(U$6-PadP$2)") (class "Default")
      (node (ref "U$6") (pin "P$2") (pinfunction "P$2_P$2") (pintype "bidirectional"))
    )
    (net (code "112") (name "unconnected-(U$7-PadP$1)") (class "Default")
      (node (ref "U$7") (pin "P$1") (pinfunction "P$1_P$1") (pintype "bidirectional"))
    )
    (net (code "113") (name "unconnected-(U$7-PadP$2)") (class "Default")
      (node (ref "U$7") (pin "P$2") (pinfunction "P$2_P$2") (pintype "bidirectional"))
    )
    (net (code "114") (name "unconnected-(U$8-PadP$1)") (class "Default")
      (node (ref "U$8") (pin "P$1") (pinfunction "P$1_P$1") (pintype "bidirectional"))
    )
    (net (code "115") (name "unconnected-(U$8-PadP$2)") (class "Default")
      (node (ref "U$8") (pin "P$2") (pinfunction "P$2_P$2") (pintype "bidirectional"))
    )
    (net (code "116") (name "unconnected-(U$9-PadP$1)") (class "Default")
      (node (ref "U$9") (pin "P$1") (pinfunction "P$1_P$1") (pintype "bidirectional"))
    )
    (net (code "117") (name "unconnected-(U$9-PadP$2)") (class "Default")
      (node (ref "U$9") (pin "P$2") (pinfunction "P$2_P$2") (pintype "bidirectional"))
    )
    (net (code "118") (name "unconnected-(U$10-PadP$1)") (class "Default")
      (node (ref "U$10") (pin "P$1") (pinfunction "P$1_P$1") (pintype "bidirectional"))
    )
    (net (code "119") (name "unconnected-(U$10-PadP$2)") (class "Default")
      (node (ref "U$10") (pin "P$2") (pinfunction "P$2_P$2") (pintype "bidirectional"))
    )
    (net (code "120") (name "unconnected-(U$11-PadP$1)") (class "Default")
      (node (ref "U$11") (pin "P$1") (pinfunction "P$1_P$1") (pintype "bidirectional"))
    )
    (net (code "121") (name "unconnected-(U$11-PadP$2)") (class "Default")
      (node (ref "U$11") (pin "P$2") (pinfunction "P$2_P$2") (pintype "bidirectional"))
    )
    (net (code "122") (name "unconnected-(U$12-PadP$1)") (class "Default")
      (node (ref "U$12") (pin "P$1") (pinfunction "P$1_P$1") (pintype "bidirectional"))
    )
    (net (code "123") (name "unconnected-(U$12-PadP$2)") (class "Default")
      (node (ref "U$12") (pin "P$2") (pinfunction "P$2_P$2") (pintype "bidirectional"))
    )
    (net (code "124") (name "unconnected-(U$13-PadP$1)") (class "Default")
      (node (ref "U$13") (pin "P$1") (pinfunction "P$1_P$1") (pintype "bidirectional"))
    )
    (net (code "125") (name "unconnected-(U$13-PadP$2)") (class "Default")
      (node (ref "U$13") (pin "P$2") (pinfunction "P$2_P$2") (pintype "bidirectional"))
    )
    (net (code "126") (name "unconnected-(U$14-PadP$1)") (class "Default")
      (node (ref "U$14") (pin "P$1") (pinfunction "P$1_P$1") (pintype "bidirectional"))
    )
    (net (code "127") (name "unconnected-(U$14-PadP$2)") (class "Default")
      (node (ref "U$14") (pin "P$2") (pinfunction "P$2_P$2") (pintype "bidirectional"))
    )
    (net (code "128") (name "unconnected-(U$15-PadP$1)") (class "Default")
      (node (ref "U$15") (pin "P$1") (pinfunction "P$1_P$1") (pintype "bidirectional"))
    )
    (net (code "129") (name "unconnected-(U$15-PadP$2)") (class "Default")
      (node (ref "U$15") (pin "P$2") (pinfunction "P$2_P$2") (pintype "bidirectional"))
    )
    (net (code "130") (name "unconnected-(U$16-PadP$1)") (class "Default")
      (node (ref "U$16") (pin "P$1") (pinfunction "P$1_P$1") (pintype "bidirectional"))
    )
    (net (code "131") (name "unconnected-(U$16-PadP$2)") (class "Default")
      (node (ref "U$16") (pin "P$2") (pinfunction "P$2_P$2") (pintype "bidirectional"))
    )
    (net (code "132") (name "unconnected-(U$17-PadP$1)") (class "Default")
      (node (ref "U$17") (pin "P$1") (pinfunction "P$1_P$1") (pintype "bidirectional"))
    )
    (net (code "133") (name "unconnected-(U$17-PadP$2)") (class "Default")
      (node (ref "U$17") (pin "P$2") (pinfunction "P$2_P$2") (pintype "bidirectional"))
    )
    (net (code "134") (name "unconnected-(U$18-PadP$1)") (class "Default")
      (node (ref "U$18") (pin "P$1") (pinfunction "P$1_P$1") (pintype "bidirectional"))
    )
    (net (code "135") (name "unconnected-(U$18-PadP$2)") (class "Default")
      (node (ref "U$18") (pin "P$2") (pinfunction "P$2_P$2") (pintype "bidirectional"))
    )
    (net (code "136") (name "unconnected-(U$19-PadP$1)") (class "Default")
      (node (ref "U$19") (pin "P$1") (pinfunction "P$1_P$1") (pintype "bidirectional"))
    )
    (net (code "137") (name "unconnected-(U$19-PadP$2)") (class "Default")
      (node (ref "U$19") (pin "P$2") (pinfunction "P$2_P$2") (pintype "bidirectional"))
    )
    (net (code "138") (name "unconnected-(U$20-PadP$1)") (class "Default")
      (node (ref "U$20") (pin "P$1") (pinfunction "P$1_P$1") (pintype "bidirectional"))
    )
    (net (code "139") (name "unconnected-(U$20-PadP$2)") (class "Default")
      (node (ref "U$20") (pin "P$2") (pinfunction "P$2_P$2") (pintype "bidirectional"))
    )
    (net (code "140") (name "unconnected-(U$21-PadP$1)") (class "Default")
      (node (ref "U$21") (pin "P$1") (pinfunction "P$1_P$1") (pintype "bidirectional"))
    )
    (net (code "141") (name "unconnected-(U$21-PadP$2)") (class "Default")
      (node (ref "U$21") (pin "P$2") (pinfunction "P$2_P$2") (pintype "bidirectional"))
    )
    (net (code "142") (name "unconnected-(U$22-PadP$1)") (class "Default")
      (node (ref "U$22") (pin "P$1") (pinfunction "P$1_P$1") (pintype "bidirectional"))
    )
    (net (code "143") (name "unconnected-(U$22-PadP$2)") (class "Default")
      (node (ref "U$22") (pin "P$2") (pinfunction "P$2_P$2") (pintype "bidirectional"))
    )
    (net (code "144") (name "unconnected-(U$23-PadP$1)") (class "Default")
      (node (ref "U$23") (pin "P$1") (pinfunction "P$1_P$1") (pintype "bidirectional"))
    )
    (net (code "145") (name "unconnected-(U$23-PadP$2)") (class "Default")
      (node (ref "U$23") (pin "P$2") (pinfunction "P$2_P$2") (pintype "bidirectional"))
    )
    (net (code "146") (name "unconnected-(U$24-PadP$1)") (class "Default")
      (node (ref "U$24") (pin "P$1") (pinfunction "P$1_P$1") (pintype "bidirectional"))
    )
    (net (code "147") (name "unconnected-(U$24-PadP$2)") (class "Default")
      (node (ref "U$24") (pin "P$2") (pinfunction "P$2_P$2") (pintype "bidirectional"))
    )
    (net (code "148") (name "unconnected-(U$25-PadP$1)") (class "Default")
      (node (ref "U$25") (pin "P$1") (pinfunction "P$1_P$1") (pintype "bidirectional"))
    )
    (net (code "149") (name "unconnected-(U$25-PadP$2)") (class "Default")
      (node (ref "U$25") (pin "P$2") (pinfunction "P$2_P$2") (pintype "bidirectional"))
    )
    (net (code "150") (name "unconnected-(U$26-PadP$1)") (class "Default")
      (node (ref "U$26") (pin "P$1") (pinfunction "P$1_P$1") (pintype "bidirectional"))
    )
    (net (code "151") (name "unconnected-(U$26-PadP$2)") (class "Default")
      (node (ref "U$26") (pin "P$2") (pinfunction "P$2_P$2") (pintype "bidirectional"))
    )
    (net (code "152") (name "unconnected-(U$27-PadP$1)") (class "Default")
      (node (ref "U$27") (pin "P$1") (pinfunction "P$1_P$1") (pintype "bidirectional"))
    )
    (net (code "153") (name "unconnected-(U$27-PadP$2)") (class "Default")
      (node (ref "U$27") (pin "P$2") (pinfunction "P$2_P$2") (pintype "bidirectional"))
    )
    (net (code "154") (name "unconnected-(U$28-PadP$1)") (class "Default")
      (node (ref "U$28") (pin "P$1") (pinfunction "P$1_P$1") (pintype "bidirectional"))
    )
    (net (code "155") (name "unconnected-(U$28-PadP$2)") (class "Default")
      (node (ref "U$28") (pin "P$2") (pinfunction "P$2_P$2") (pintype "bidirectional"))
    )
    (net (code "156") (name "unconnected-(U$29-PadP$1)") (class "Default")
      (node (ref "U$29") (pin "P$1") (pinfunction "P$1_P$1") (pintype "bidirectional"))
    )
    (net (code "157") (name "unconnected-(U$29-PadP$2)") (class "Default")
      (node (ref "U$29") (pin "P$2") (pinfunction "P$2_P$2") (pintype "bidirectional"))
    )
    (net (code "158") (name "unconnected-(U$30-PadP$1)") (class "Default")
      (node (ref "U$30") (pin "P$1") (pinfunction "P$1_P$1") (pintype "bidirectional"))
    )
    (net (code "159") (name "unconnected-(U$30-PadP$2)") (class "Default")
      (node (ref "U$30") (pin "P$2") (pinfunction "P$2_P$2") (pintype "bidirectional"))
    )
    (net (code "160") (name "unconnected-(U$31-PadP$1)") (class "Default")
      (node (ref "U$31") (pin "P$1") (pinfunction "P$1_P$1") (pintype "bidirectional"))
    )
    (net (code "161") (name "unconnected-(U$31-PadP$2)") (class "Default")
      (node (ref "U$31") (pin "P$2") (pinfunction "P$2_P$2") (pintype "bidirectional"))
    )
    (net (code "162") (name "unconnected-(U$32-PadP$1)") (class "Default")
      (node (ref "U$32") (pin "P$1") (pinfunction "P$1_P$1") (pintype "bidirectional"))
    )
    (net (code "163") (name "unconnected-(U$32-PadP$2)") (class "Default")
      (node (ref "U$32") (pin "P$2") (pinfunction "P$2_P$2") (pintype "bidirectional"))
    )
    (net (code "164") (name "unconnected-(U$33-PadP$1)") (class "Default")
      (node (ref "U$33") (pin "P$1") (pinfunction "P$1_P$1") (pintype "bidirectional"))
    )
    (net (code "165") (name "unconnected-(U$33-PadP$2)") (class "Default")
      (node (ref "U$33") (pin "P$2") (pinfunction "P$2_P$2") (pintype "bidirectional"))
    )
    (net (code "166") (name "unconnected-(U$34-PadP$1)") (class "Default")
      (node (ref "U$34") (pin "P$1") (pinfunction "P$1_P$1") (pintype "bidirectional"))
    )
    (net (code "167") (name "unconnected-(U$34-PadP$2)") (class "Default")
      (node (ref "U$34") (pin "P$2") (pinfunction "P$2_P$2") (pintype "bidirectional"))
    )
    (net (code "168") (name "unconnected-(U$36-PadP$1)") (class "Default")
      (node (ref "U$36") (pin "P$1") (pinfunction "P$1_P$1") (pintype "bidirectional"))
    )
    (net (code "169") (name "unconnected-(U$36-PadP$2)") (class "Default")
      (node (ref "U$36") (pin "P$2") (pinfunction "P$2_P$2") (pintype "bidirectional"))
    )
  )
)
